# FLC100_level_shifting.net
KiCad netlist of a schematic drawn in EAGLE
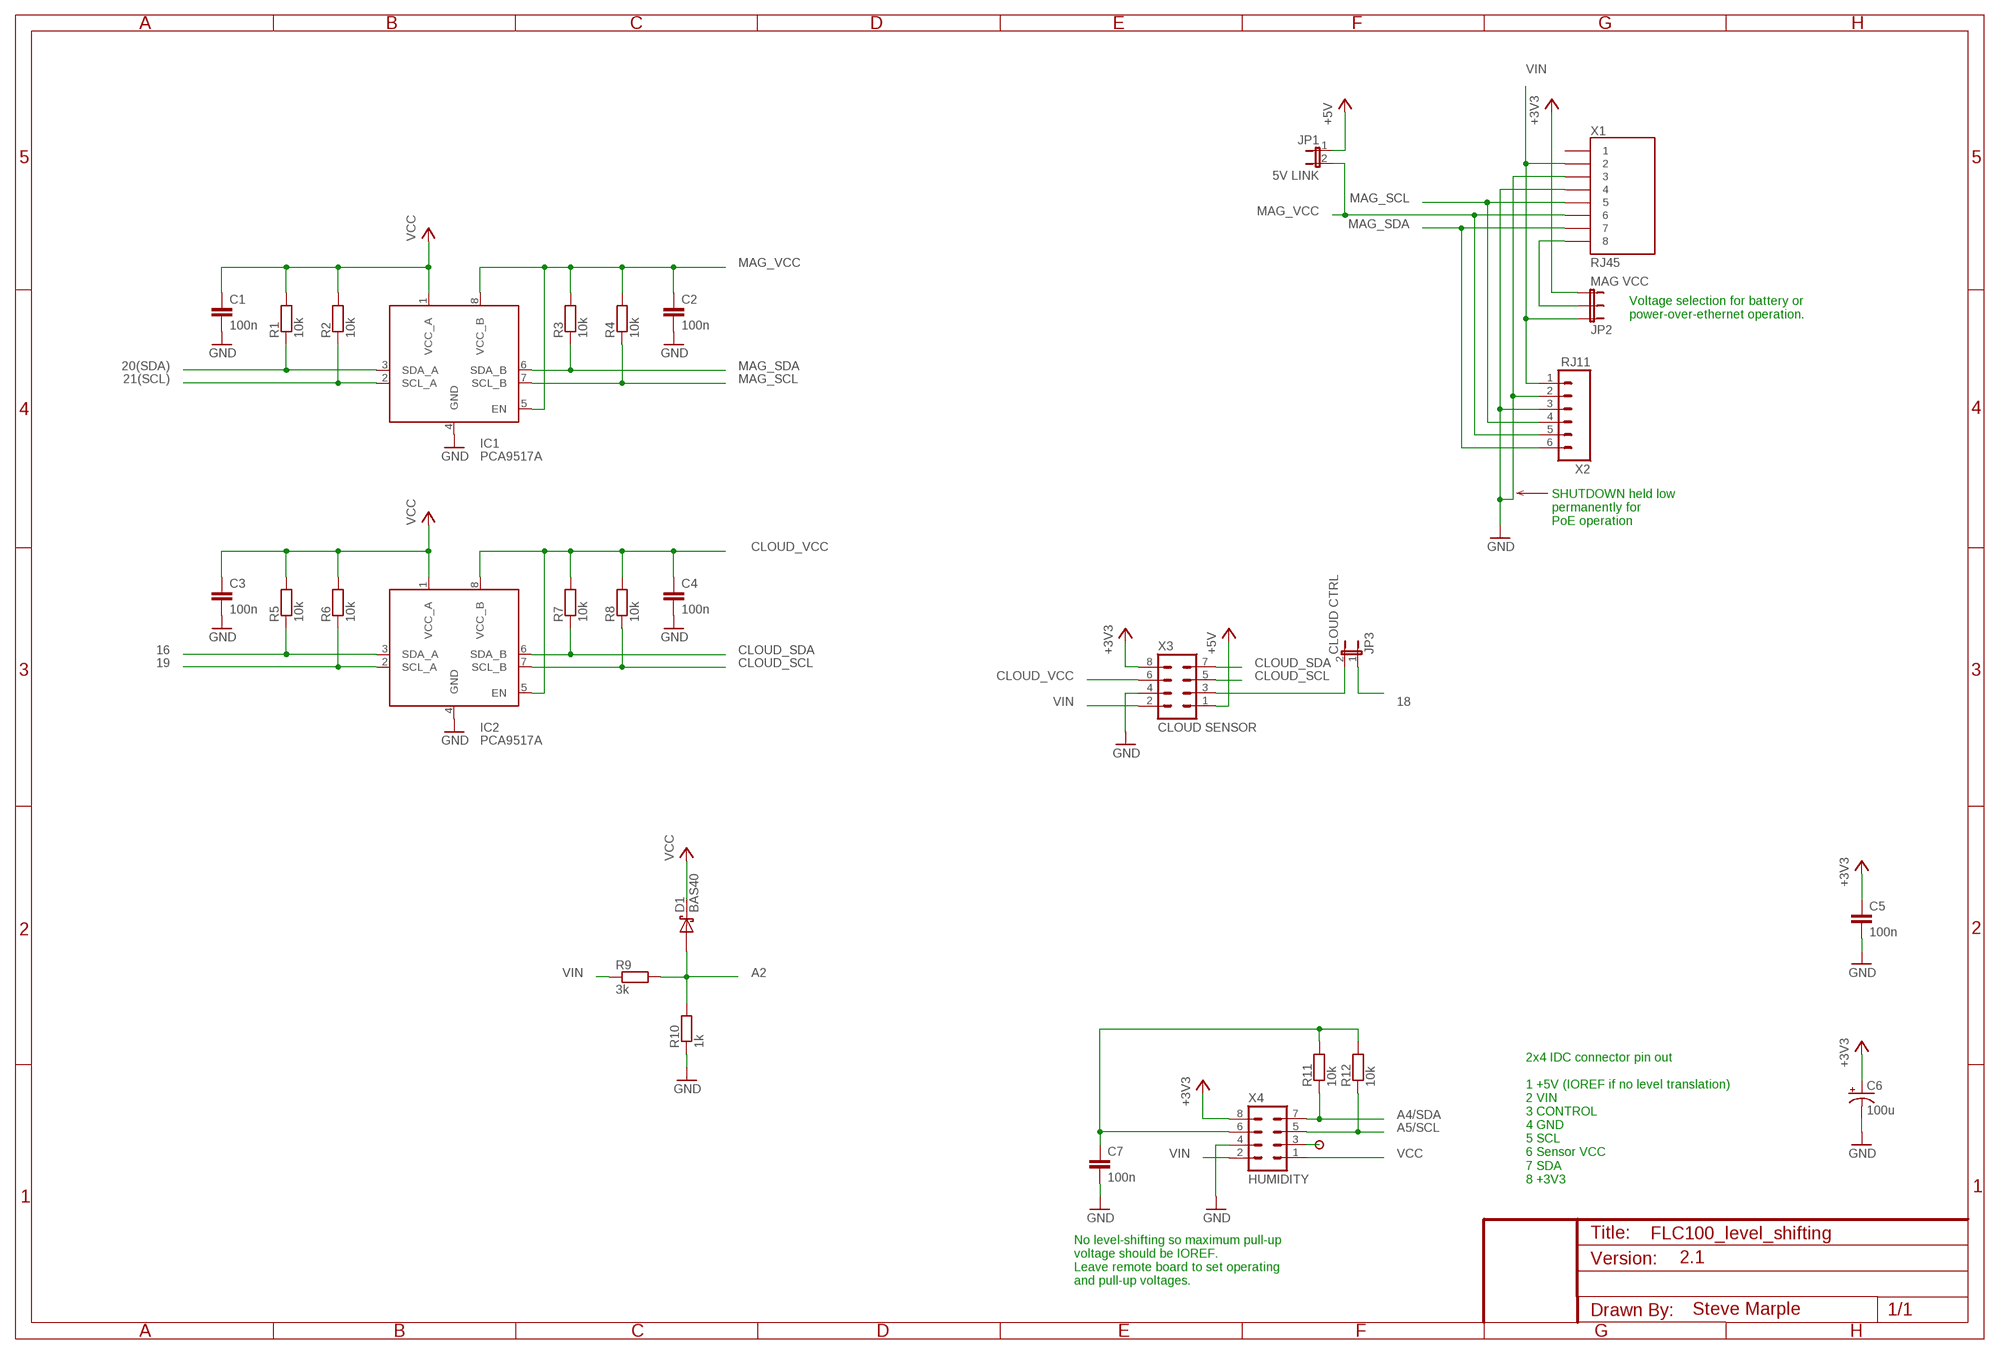
[diagram p0: schematic, sheet 1]

(export (version "E")
  (design (tool "Eeschema 10.0.6"))
  (components
    (comp (ref "C1")
      (value "100n")
      (footprint "eagle-import:1206-HAND")
      (libsource (lib "eagle-import") (part "C-EU1206-HAND"))
    )
    (comp (ref "C2")
      (value "100n")
      (footprint "eagle-import:1206-HAND")
      (libsource (lib "eagle-import") (part "C-EU1206-HAND"))
    )
    (comp (ref "C3")
      (value "100n")
      (footprint "eagle-import:1206-HAND")
      (libsource (lib "eagle-import") (part "C-EU1206-HAND"))
    )
    (comp (ref "C4")
      (value "100n")
      (footprint "eagle-import:1206-HAND")
      (libsource (lib "eagle-import") (part "C-EU1206-HAND"))
    )
    (comp (ref "C5")
      (value "100n")
      (footprint "eagle-import:1206-HAND")
      (libsource (lib "eagle-import") (part "C-EU1206-HAND"))
    )
    (comp (ref "C6")
      (value "100u")
      (footprint "eagle-import:CPOL-RADIAL-10UF-25V")
      (libsource (lib "eagle-import") (part "CAP_POLPTH2"))
    )
    (comp (ref "C7")
      (value "100n")
      (footprint "eagle-import:1206-HAND")
      (libsource (lib "eagle-import") (part "C-EU1206-HAND"))
    )
    (comp (ref "D1")
      (value "BAS40")
      (footprint "eagle-import:SOT23-3-HAND")
      (libsource (lib "eagle-import") (part "DIODE-SCHOTTKYSOT23-1-3-HAND"))
    )
    (comp (ref "IC1")
      (value "PCA9517A")
      (footprint "eagle-import:SO08")
      (libsource (lib "eagle-import") (part "PCA9517ASOIC"))
    )
    (comp (ref "IC2")
      (value "PCA9517A")
      (footprint "eagle-import:SO08")
      (libsource (lib "eagle-import") (part "PCA9517ASOIC"))
    )
    (comp (ref "JP1")
      (value "5V LINK")
      (footprint "eagle-import:1X02")
      (libsource (lib "eagle-import") (part "JUMPER-2PTH"))
    )
    (comp (ref "JP2")
      (value "MAG VCC")
      (footprint "eagle-import:1X03")
      (libsource (lib "eagle-import") (part "JUMPER-3PTH"))
    )
    (comp (ref "JP3")
      (value "CLOUD CTRL")
      (footprint "eagle-import:1X02")
      (libsource (lib "eagle-import") (part "JUMPER-2PTH"))
    )
    (comp (ref "R1")
      (value "10k")
      (footprint "eagle-import:1206-HAND")
      (libsource (lib "eagle-import") (part "RESISTOR1206-HAND"))
    )
    (comp (ref "R2")
      (value "10k")
      (footprint "eagle-import:1206-HAND")
      (libsource (lib "eagle-import") (part "RESISTOR1206-HAND"))
    )
    (comp (ref "R3")
      (value "10k")
      (footprint "eagle-import:1206-HAND")
      (libsource (lib "eagle-import") (part "RESISTOR1206-HAND"))
    )
    (comp (ref "R4")
      (value "10k")
      (footprint "eagle-import:1206-HAND")
      (libsource (lib "eagle-import") (part "RESISTOR1206-HAND"))
    )
    (comp (ref "R5")
      (value "10k")
      (footprint "eagle-import:1206-HAND")
      (libsource (lib "eagle-import") (part "RESISTOR1206-HAND"))
    )
    (comp (ref "R6")
      (value "10k")
      (footprint "eagle-import:1206-HAND")
      (libsource (lib "eagle-import") (part "RESISTOR1206-HAND"))
    )
    (comp (ref "R7")
      (value "10k")
      (footprint "eagle-import:1206-HAND")
      (libsource (lib "eagle-import") (part "RESISTOR1206-HAND"))
    )
    (comp (ref "R8")
      (value "10k")
      (footprint "eagle-import:1206-HAND")
      (libsource (lib "eagle-import") (part "RESISTOR1206-HAND"))
    )
    (comp (ref "R9")
      (value "3k")
      (footprint "eagle-import:1206-HAND")
      (libsource (lib "eagle-import") (part "RESISTOR1206-HAND"))
    )
    (comp (ref "R10")
      (value "1k")
      (footprint "eagle-import:1206-HAND")
      (libsource (lib "eagle-import") (part "RESISTOR1206-HAND"))
    )
    (comp (ref "R11")
      (value "10k")
      (footprint "eagle-import:1206-HAND")
      (libsource (lib "eagle-import") (part "RESISTOR1206-HAND"))
    )
    (comp (ref "R12")
      (value "10k")
      (footprint "eagle-import:1206-HAND")
      (libsource (lib "eagle-import") (part "RESISTOR1206-HAND"))
    )
    (comp (ref "U$5")
      (value "PAD")
      (footprint "eagle-import:PAD")
      (libsource (lib "eagle-import") (part "PAD"))
    )
    (comp (ref "X1")
      (value "RJ45")
      (footprint "eagle-import:RJ45-8")
      (libsource (lib "eagle-import") (part "RJ45-8PTH"))
    )
    (comp (ref "X2")
      (value "RJ11")
      (footprint "eagle-import:RJ11-6")
      (libsource (lib "eagle-import") (part "RJ11-6PTH"))
    )
    (comp (ref "X3")
      (value "CLOUD SENSOR")
      (footprint "eagle-import:ML8")
      (libsource (lib "eagle-import") (part "ML8"))
    )
    (comp (ref "X4")
      (value "HUMIDITY")
      (footprint "eagle-import:ML8")
      (libsource (lib "eagle-import") (part "ML8"))
    )
  )
  (nets
    (net (code "1") (name "+3V3") (class "Default")
      (node (ref "C5") (pin "1") (pinfunction "1_1") (pintype "passive"))
      (node (ref "C6") (pin "1") (pinfunction "+_1") (pintype "passive"))
      (node (ref "JP2") (pin "3") (pinfunction "3_3") (pintype "passive"))
      (node (ref "X3") (pin "8") (pinfunction "8_8") (pintype "passive"))
      (node (ref "X4") (pin "8") (pinfunction "8_8") (pintype "passive"))
    )
    (net (code "2") (name "+5V") (class "Default")
      (node (ref "JP1") (pin "1") (pinfunction "1_1") (pintype "passive"))
      (node (ref "X3") (pin "1") (pinfunction "1_1") (pintype "passive"))
    )
    (net (code "3") (name "/16") (class "Default")
      (node (ref "IC2") (pin "3") (pinfunction "SDA_A_3") (pintype "bidirectional"))
      (node (ref "R5") (pin "1") (pinfunction "1_1") (pintype "passive"))
    )
    (net (code "4") (name "/18") (class "Default")
      (node (ref "JP3") (pin "1") (pinfunction "1_1") (pintype "passive"))
    )
    (net (code "5") (name "/19") (class "Default")
      (node (ref "IC2") (pin "2") (pinfunction "SCL_A_2") (pintype "bidirectional"))
      (node (ref "R6") (pin "1") (pinfunction "1_1") (pintype "passive"))
    )
    (net (code "6") (name "/20(SDA)") (class "Default")
      (node (ref "IC1") (pin "3") (pinfunction "SDA_A_3") (pintype "bidirectional"))
      (node (ref "R1") (pin "1") (pinfunction "1_1") (pintype "passive"))
    )
    (net (code "7") (name "/21(SCL)") (class "Default")
      (node (ref "IC1") (pin "2") (pinfunction "SCL_A_2") (pintype "bidirectional"))
      (node (ref "R2") (pin "1") (pinfunction "1_1") (pintype "passive"))
    )
    (net (code "8") (name "/A2") (class "Default")
      (node (ref "D1") (pin "1") (pinfunction "A_1") (pintype "passive"))
      (node (ref "R10") (pin "2") (pinfunction "2_2") (pintype "passive"))
      (node (ref "R9") (pin "2") (pinfunction "2_2") (pintype "passive"))
    )
    (net (code "9") (name "/A4{slash}SDA") (class "Default")
      (node (ref "R11") (pin "1") (pinfunction "1_1") (pintype "passive"))
      (node (ref "X4") (pin "7") (pinfunction "7_7") (pintype "passive"))
    )
    (net (code "10") (name "/A5{slash}SCL") (class "Default")
      (node (ref "R12") (pin "1") (pinfunction "1_1") (pintype "passive"))
      (node (ref "X4") (pin "5") (pinfunction "5_5") (pintype "passive"))
    )
    (net (code "11") (name "/CLOUD_SCL") (class "Default")
      (node (ref "IC2") (pin "7") (pinfunction "SCL_B_7") (pintype "bidirectional"))
      (node (ref "R8") (pin "1") (pinfunction "1_1") (pintype "passive"))
      (node (ref "X3") (pin "5") (pinfunction "5_5") (pintype "passive"))
    )
    (net (code "12") (name "/CLOUD_SDA") (class "Default")
      (node (ref "IC2") (pin "6") (pinfunction "SDA_B_6") (pintype "bidirectional"))
      (node (ref "R7") (pin "1") (pinfunction "1_1") (pintype "passive"))
      (node (ref "X3") (pin "7") (pinfunction "7_7") (pintype "passive"))
    )
    (net (code "13") (name "/CLOUD_VCC") (class "Default")
      (node (ref "C4") (pin "1") (pinfunction "1_1") (pintype "passive"))
      (node (ref "IC2") (pin "5") (pinfunction "EN_5") (pintype "bidirectional"))
      (node (ref "IC2") (pin "8") (pinfunction "VCC_B_8") (pintype "power_in"))
      (node (ref "R7") (pin "2") (pinfunction "2_2") (pintype "passive"))
      (node (ref "R8") (pin "2") (pinfunction "2_2") (pintype "passive"))
      (node (ref "X3") (pin "6") (pinfunction "6_6") (pintype "passive"))
    )
    (net (code "14") (name "/MAG_SCL") (class "Default")
      (node (ref "IC1") (pin "7") (pinfunction "SCL_B_7") (pintype "bidirectional"))
      (node (ref "R4") (pin "1") (pinfunction "1_1") (pintype "passive"))
      (node (ref "X1") (pin "5") (pinfunction "5_5") (pintype "bidirectional"))
      (node (ref "X2") (pin "4") (pinfunction "4_4") (pintype "passive"))
    )
    (net (code "15") (name "/MAG_SDA") (class "Default")
      (node (ref "IC1") (pin "6") (pinfunction "SDA_B_6") (pintype "bidirectional"))
      (node (ref "R3") (pin "1") (pinfunction "1_1") (pintype "passive"))
      (node (ref "X1") (pin "7") (pinfunction "7_7") (pintype "bidirectional"))
      (node (ref "X2") (pin "6") (pinfunction "6_6") (pintype "passive"))
    )
    (net (code "16") (name "/MAG_VCC") (class "Default")
      (node (ref "C2") (pin "1") (pinfunction "1_1") (pintype "passive"))
      (node (ref "IC1") (pin "5") (pinfunction "EN_5") (pintype "bidirectional"))
      (node (ref "IC1") (pin "8") (pinfunction "VCC_B_8") (pintype "power_in"))
      (node (ref "JP1") (pin "2") (pinfunction "2_2") (pintype "passive"))
      (node (ref "R3") (pin "2") (pinfunction "2_2") (pintype "passive"))
      (node (ref "R4") (pin "2") (pinfunction "2_2") (pintype "passive"))
      (node (ref "X1") (pin "6") (pinfunction "6_6") (pintype "bidirectional"))
      (node (ref "X2") (pin "5") (pinfunction "5_5") (pintype "passive"))
    )
    (net (code "17") (name "/VIN") (class "Default")
      (node (ref "JP2") (pin "1") (pinfunction "1_1") (pintype "passive"))
      (node (ref "R9") (pin "1") (pinfunction "1_1") (pintype "passive"))
      (node (ref "X1") (pin "2") (pinfunction "2_2") (pintype "bidirectional"))
      (node (ref "X2") (pin "1") (pinfunction "1_1") (pintype "passive"))
      (node (ref "X3") (pin "2") (pinfunction "2_2") (pintype "passive"))
      (node (ref "X4") (pin "2") (pinfunction "2_2") (pintype "passive"))
    )
    (net (code "18") (name "GND") (class "Default")
      (node (ref "C1") (pin "2") (pinfunction "2_2") (pintype "passive"))
      (node (ref "C2") (pin "2") (pinfunction "2_2") (pintype "passive"))
      (node (ref "C3") (pin "2") (pinfunction "2_2") (pintype "passive"))
      (node (ref "C4") (pin "2") (pinfunction "2_2") (pintype "passive"))
      (node (ref "C5") (pin "2") (pinfunction "2_2") (pintype "passive"))
      (node (ref "C6") (pin "2") (pinfunction "-_2") (pintype "passive"))
      (node (ref "C7") (pin "2") (pinfunction "2_2") (pintype "passive"))
      (node (ref "IC1") (pin "4") (pinfunction "GND_4") (pintype "power_in"))
      (node (ref "IC2") (pin "4") (pinfunction "GND_4") (pintype "power_in"))
      (node (ref "R10") (pin "1") (pinfunction "1_1") (pintype "passive"))
      (node (ref "X1") (pin "3") (pinfunction "3_3") (pintype "bidirectional"))
      (node (ref "X1") (pin "4") (pinfunction "4_4") (pintype "bidirectional"))
      (node (ref "X2") (pin "2") (pinfunction "2_2") (pintype "passive"))
      (node (ref "X2") (pin "3") (pinfunction "3_3") (pintype "passive"))
      (node (ref "X3") (pin "4") (pinfunction "4_4") (pintype "passive"))
      (node (ref "X4") (pin "4") (pinfunction "4_4") (pintype "passive"))
    )
    (net (code "19") (name "Net-(C7-Pad1)") (class "Default")
      (node (ref "C7") (pin "1") (pinfunction "1_1") (pintype "passive"))
      (node (ref "R11") (pin "2") (pinfunction "2_2") (pintype "passive"))
      (node (ref "R12") (pin "2") (pinfunction "2_2") (pintype "passive"))
      (node (ref "X4") (pin "6") (pinfunction "6_6") (pintype "passive"))
    )
    (net (code "20") (name "Net-(JP2-Pad2)") (class "Default")
      (node (ref "JP2") (pin "2") (pinfunction "2_2") (pintype "passive"))
      (node (ref "X1") (pin "8") (pinfunction "8_8") (pintype "bidirectional"))
    )
    (net (code "21") (name "Net-(JP3-Pad2)") (class "Default")
      (node (ref "JP3") (pin "2") (pinfunction "2_2") (pintype "passive"))
      (node (ref "X3") (pin "3") (pinfunction "3_3") (pintype "passive"))
    )
    (net (code "22") (name "Net-(U$5-Pad1)") (class "Default")
      (node (ref "U$5") (pin "1") (pinfunction "1_1") (pintype "bidirectional"))
      (node (ref "X4") (pin "3") (pinfunction "3_3") (pintype "passive"))
    )
    (net (code "23") (name "VCC") (class "Default")
      (node (ref "C1") (pin "1") (pinfunction "1_1") (pintype "passive"))
      (node (ref "C3") (pin "1") (pinfunction "1_1") (pintype "passive"))
      (node (ref "D1") (pin "3") (pinfunction "C_3") (pintype "passive"))
      (node (ref "IC1") (pin "1") (pinfunction "VCC_A_1") (pintype "power_in"))
      (node (ref "IC2") (pin "1") (pinfunction "VCC_A_1") (pintype "power_in"))
      (node (ref "R1") (pin "2") (pinfunction "2_2") (pintype "passive"))
      (node (ref "R2") (pin "2") (pinfunction "2_2") (pintype "passive"))
      (node (ref "R5") (pin "2") (pinfunction "2_2") (pintype "passive"))
      (node (ref "R6") (pin "2") (pinfunction "2_2") (pintype "passive"))
      (node (ref "X4") (pin "1") (pinfunction "1_1") (pintype "passive"))
    )
    (net (code "24") (name "unconnected-(X1-Pad1)") (class "Default")
      (node (ref "X1") (pin "1") (pinfunction "1_1") (pintype "bidirectional"))
    )
  )
)
